# gpr01.net
KiCad netlist of a schematic drawn in EAGLE
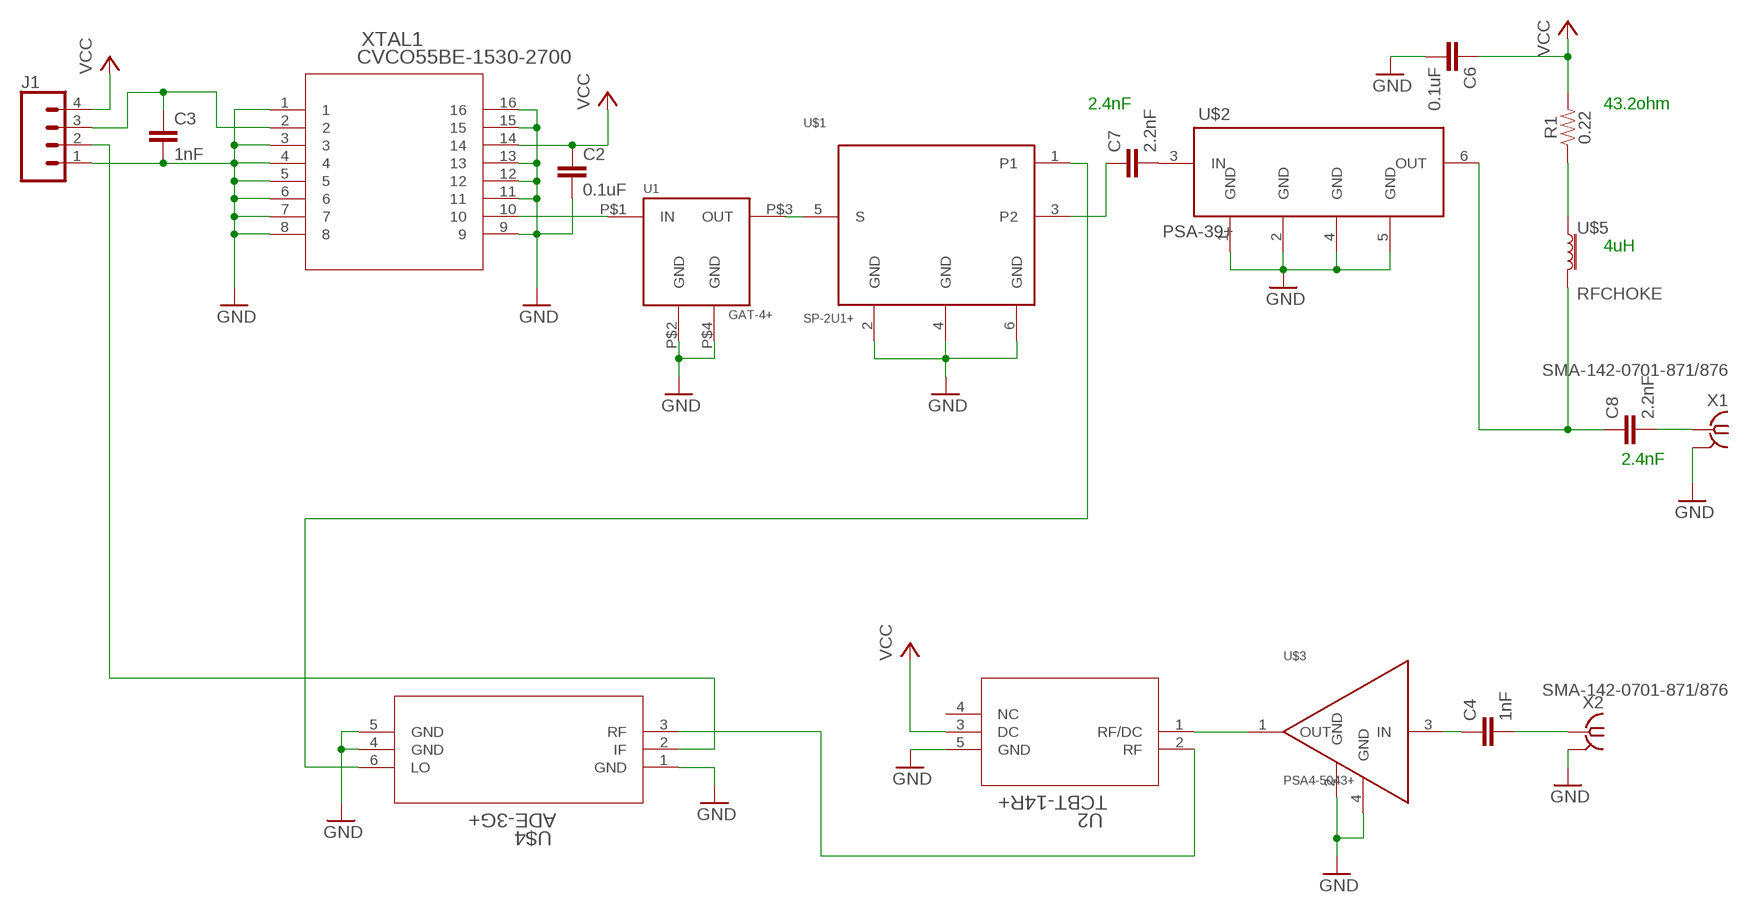
[diagram p0: schematic, sheet 1]

(export (version "E")
  (design (tool "Eeschema 10.0.6"))
  (components
    (comp (ref "C2")
      (value "0.1uF")
      (footprint "eagle-import:0402")
      (libsource (lib "eagle-import") (part "0.1UF-0402-16V-10%"))
    )
    (comp (ref "C3")
      (value "1nF")
      (footprint "eagle-import:0603")
      (libsource (lib "eagle-import") (part "1.0NF/1000PF-0603-50V-10%"))
    )
    (comp (ref "C4")
      (value "1nF")
      (footprint "eagle-import:0603")
      (libsource (lib "eagle-import") (part "1.0NF/1000PF-0603-50V-10%"))
    )
    (comp (ref "C6")
      (value "0.1uF")
      (footprint "eagle-import:0402")
      (libsource (lib "eagle-import") (part "0.1UF-0402-16V-10%"))
    )
    (comp (ref "C7")
      (value "2.2nF")
      (footprint "eagle-import:0603")
      (libsource (lib "eagle-import") (part "2.2NF/2200PF-0603-50V-10%"))
    )
    (comp (ref "C8")
      (value "2.2nF")
      (footprint "eagle-import:0603")
      (libsource (lib "eagle-import") (part "2.2NF/2200PF-0603-50V-10%"))
    )
    (comp (ref "J1")
      (value "CONN_04POLAR")
      (footprint "eagle-import:MOLEX-1X4")
      (libsource (lib "eagle-import") (part "CONN_04POLAR"))
    )
    (comp (ref "R1")
      (value "0.22")
      (footprint "eagle-import:0805")
      (libsource (lib "eagle-import") (part "0.22OHM-0805-1/4W-1%"))
    )
    (comp (ref "U$1")
      (value "SP-2U1+")
      (footprint "eagle-import:SOT23-6")
      (libsource (lib "eagle-import") (part "SP-2U1+"))
    )
    (comp (ref "U$2")
      (value "PSA-39+")
      (footprint "eagle-import:SOT363_PHILIPS")
      (libsource (lib "eagle-import") (part "PSA-39+"))
    )
    (comp (ref "U$3")
      (value "PSA4-5043+")
      (footprint "eagle-import:SOT343")
      (libsource (lib "eagle-import") (part "PSA4-5043+"))
    )
    (comp (ref "U$4")
      (value "ADE-3G+")
      (footprint "eagle-import:CD542_MNC")
      (libsource (lib "eagle-import") (part "ADE-3G+"))
    )
    (comp (ref "U$5")
      (value "RFCHOKE")
      (footprint "eagle-import:1210")
      (libsource (lib "eagle-import") (part "RFCHOKE"))
    )
    (comp (ref "U1")
      (value "GAT-4+")
      (footprint "eagle-import:GAT-4+")
      (libsource (lib "eagle-import") (part "GAT-4+"))
    )
    (comp (ref "U2")
      (value "TCBT-14R+")
      (footprint "eagle-import:GU1414-2_MNC")
      (fields (field (name "COPYRIGHT") "Copyright (C) 2018 Accelerated Designs. All rights reserved"))
      (libsource (lib "eagle-import") (part "TCBT-14R+"))
    )
    (comp (ref "X1")
      (value "SMA-142-0701-871/876")
      (footprint "eagle-import:J502-ND-142-0701-871_876")
      (fields (field (name "MF") "JOHNSON COMPONENTS") (field (name "MPN") "142-0701-871"))
      (libsource (lib "eagle-import") (part "SMA-142-0701-871/876"))
    )
    (comp (ref "X2")
      (value "SMA-142-0701-871/876")
      (footprint "eagle-import:J502-ND-142-0701-871_876")
      (fields (field (name "MF") "JOHNSON COMPONENTS") (field (name "MPN") "142-0701-871"))
      (libsource (lib "eagle-import") (part "SMA-142-0701-871/876"))
    )
    (comp (ref "XTAL1")
      (value "CVCO55BE-1530-2700")
      (footprint "eagle-import:CVCO55BE-1530-2700_CRX")
      (fields (field (name "COPYRIGHT") "Copyright (C) 2018 Accelerated Designs. All rights reserved"))
      (libsource (lib "eagle-import") (part "CVCO55BE-1530-2700"))
    )
  )
  (nets
    (net (code "1") (name "GND") (class "Default")
      (node (ref "C2") (pin "2") (pinfunction "2_2") (pintype "passive"))
      (node (ref "C3") (pin "2") (pinfunction "2_2") (pintype "passive"))
      (node (ref "C6") (pin "2") (pinfunction "2_2") (pintype "passive"))
      (node (ref "J1") (pin "1") (pinfunction "1_1") (pintype "passive"))
      (node (ref "U$1") (pin "2") (pinfunction "GND_2") (pintype "bidirectional"))
      (node (ref "U$1") (pin "4") (pinfunction "GND_4") (pintype "bidirectional"))
      (node (ref "U$1") (pin "6") (pinfunction "GND_6") (pintype "bidirectional"))
      (node (ref "U$2") (pin "1") (pinfunction "GND_1") (pintype "power_in"))
      (node (ref "U$2") (pin "2") (pinfunction "GND_2") (pintype "power_in"))
      (node (ref "U$2") (pin "4") (pinfunction "GND_4") (pintype "power_in"))
      (node (ref "U$2") (pin "5") (pinfunction "GND_5") (pintype "power_in"))
      (node (ref "U$3") (pin "2") (pinfunction "GND_2") (pintype "bidirectional"))
      (node (ref "U$3") (pin "4") (pinfunction "GND_4") (pintype "bidirectional"))
      (node (ref "U$4") (pin "1") (pinfunction "GND_1") (pintype "passive"))
      (node (ref "U$4") (pin "4") (pinfunction "GND_4") (pintype "passive"))
      (node (ref "U$4") (pin "5") (pinfunction "GND_5") (pintype "passive"))
      (node (ref "U1") (pin "P$2") (pinfunction "GND_P$2") (pintype "power_in"))
      (node (ref "U1") (pin "P$4") (pinfunction "GND_P$4") (pintype "power_in"))
      (node (ref "U2") (pin "5") (pinfunction "GND_5") (pintype "passive"))
      (node (ref "X1") (pin "G@1") (pinfunction "2_G@1") (pintype "passive"))
      (node (ref "X1") (pin "G@2") (pinfunction "2_G@2") (pintype "passive"))
      (node (ref "X1") (pin "G@3") (pinfunction "2_G@3") (pintype "passive"))
      (node (ref "X1") (pin "G@4") (pinfunction "2_G@4") (pintype "passive"))
      (node (ref "X2") (pin "G@1") (pinfunction "2_G@1") (pintype "passive"))
      (node (ref "X2") (pin "G@2") (pinfunction "2_G@2") (pintype "passive"))
      (node (ref "X2") (pin "G@3") (pinfunction "2_G@3") (pintype "passive"))
      (node (ref "X2") (pin "G@4") (pinfunction "2_G@4") (pintype "passive"))
      (node (ref "XTAL1") (pin "1") (pinfunction "1_1") (pintype "passive"))
      (node (ref "XTAL1") (pin "11") (pinfunction "11_11") (pintype "passive"))
      (node (ref "XTAL1") (pin "12") (pinfunction "12_12") (pintype "passive"))
      (node (ref "XTAL1") (pin "13") (pinfunction "13_13") (pintype "passive"))
      (node (ref "XTAL1") (pin "15") (pinfunction "15_15") (pintype "passive"))
      (node (ref "XTAL1") (pin "16") (pinfunction "16_16") (pintype "passive"))
      (node (ref "XTAL1") (pin "3") (pinfunction "3_3") (pintype "passive"))
      (node (ref "XTAL1") (pin "4") (pinfunction "4_4") (pintype "passive"))
      (node (ref "XTAL1") (pin "5") (pinfunction "5_5") (pintype "passive"))
      (node (ref "XTAL1") (pin "6") (pinfunction "6_6") (pintype "passive"))
      (node (ref "XTAL1") (pin "7") (pinfunction "7_7") (pintype "passive"))
      (node (ref "XTAL1") (pin "8") (pinfunction "8_8") (pintype "passive"))
      (node (ref "XTAL1") (pin "9") (pinfunction "9_9") (pintype "passive"))
    )
    (net (code "2") (name "Net-(C3-Pad1)") (class "Default")
      (node (ref "C3") (pin "1") (pinfunction "1_1") (pintype "passive"))
      (node (ref "J1") (pin "3") (pinfunction "3_3") (pintype "passive"))
      (node (ref "XTAL1") (pin "2") (pinfunction "2_2") (pintype "passive"))
    )
    (net (code "3") (name "Net-(C4-Pad2)") (class "Default")
      (node (ref "C4") (pin "2") (pinfunction "2_2") (pintype "passive"))
      (node (ref "X2") (pin "1") (pinfunction "1_1") (pintype "passive"))
    )
    (net (code "4") (name "Net-(C8-Pad2)") (class "Default")
      (node (ref "C8") (pin "2") (pinfunction "2_2") (pintype "passive"))
      (node (ref "X1") (pin "1") (pinfunction "1_1") (pintype "passive"))
    )
    (net (code "5") (name "Net-(R1-Pad1)") (class "Default")
      (node (ref "R1") (pin "1") (pinfunction "1_1") (pintype "passive"))
      (node (ref "U$5") (pin "1") (pinfunction "1_1") (pintype "passive"))
    )
    (net (code "6") (name "Net-(U$1-P1)") (class "Default")
      (node (ref "U$1") (pin "1") (pinfunction "P1_1") (pintype "bidirectional"))
      (node (ref "U$4") (pin "6") (pinfunction "LO_6") (pintype "passive"))
    )
    (net (code "7") (name "Net-(U$1-P2)") (class "Default")
      (node (ref "C7") (pin "1") (pinfunction "1_1") (pintype "passive"))
      (node (ref "U$1") (pin "3") (pinfunction "P2_3") (pintype "bidirectional"))
    )
    (net (code "8") (name "Net-(U$1-S)") (class "Default")
      (node (ref "U$1") (pin "5") (pinfunction "S_5") (pintype "bidirectional"))
      (node (ref "U1") (pin "P$3") (pinfunction "OUT_P$3") (pintype "bidirectional"))
    )
    (net (code "9") (name "Net-(U$2-IN)") (class "Default")
      (node (ref "C7") (pin "2") (pinfunction "2_2") (pintype "passive"))
      (node (ref "U$2") (pin "3") (pinfunction "IN_3") (pintype "bidirectional"))
    )
    (net (code "10") (name "Net-(U$2-OUT)") (class "Default")
      (node (ref "C8") (pin "1") (pinfunction "1_1") (pintype "passive"))
      (node (ref "U$2") (pin "6") (pinfunction "OUT_6") (pintype "bidirectional"))
      (node (ref "U$5") (pin "2") (pinfunction "2_2") (pintype "passive"))
    )
    (net (code "11") (name "Net-(U$3-IN)") (class "Default")
      (node (ref "C4") (pin "1") (pinfunction "1_1") (pintype "passive"))
      (node (ref "U$3") (pin "3") (pinfunction "IN_3") (pintype "bidirectional"))
    )
    (net (code "12") (name "Net-(U$3-OUT)") (class "Default")
      (node (ref "U$3") (pin "1") (pinfunction "OUT_1") (pintype "bidirectional"))
      (node (ref "U2") (pin "1") (pinfunction "RF/DC_1") (pintype "passive"))
    )
    (net (code "13") (name "Net-(U$4-IF)") (class "Default")
      (node (ref "J1") (pin "2") (pinfunction "2_2") (pintype "passive"))
      (node (ref "U$4") (pin "2") (pinfunction "IF_2") (pintype "passive"))
    )
    (net (code "14") (name "Net-(U$4-RF)") (class "Default")
      (node (ref "U$4") (pin "3") (pinfunction "RF_3") (pintype "passive"))
      (node (ref "U2") (pin "2") (pinfunction "RF_2") (pintype "passive"))
    )
    (net (code "15") (name "Net-(U1-IN)") (class "Default")
      (node (ref "U1") (pin "P$1") (pinfunction "IN_P$1") (pintype "bidirectional"))
      (node (ref "XTAL1") (pin "10") (pinfunction "10_10") (pintype "passive"))
    )
    (net (code "16") (name "VCC") (class "Default")
      (node (ref "C2") (pin "1") (pinfunction "1_1") (pintype "passive"))
      (node (ref "C6") (pin "1") (pinfunction "1_1") (pintype "passive"))
      (node (ref "J1") (pin "4") (pinfunction "4_4") (pintype "passive"))
      (node (ref "R1") (pin "2") (pinfunction "2_2") (pintype "passive"))
      (node (ref "U2") (pin "3") (pinfunction "DC_3") (pintype "passive"))
      (node (ref "XTAL1") (pin "14") (pinfunction "14_14") (pintype "passive"))
    )
    (net (code "17") (name "unconnected-(U2-NC-Pad4)") (class "Default")
      (node (ref "U2") (pin "4") (pinfunction "NC_4") (pintype "no_connect"))
    )
  )
)
